# Vref.net
KiCad netlist of a schematic drawn in Altium Designer
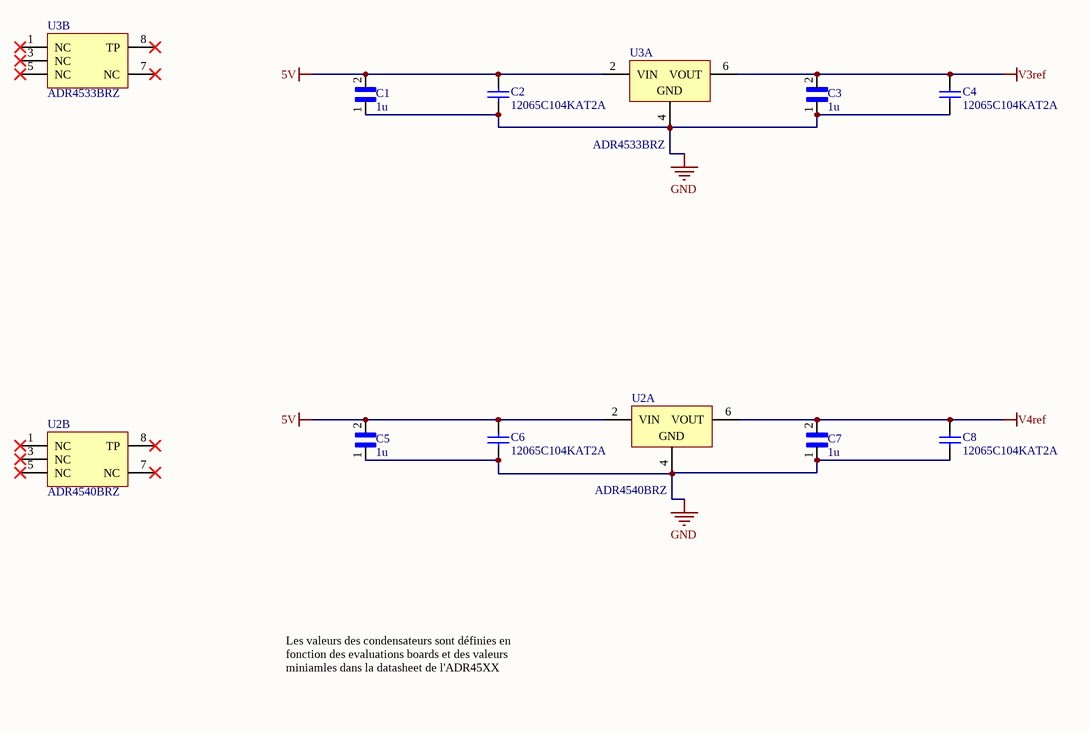
[diagram p0: Vref.SchDoc]

(export (version "E")
  (design (tool "Eeschema 10.0.6"))
  (components
    (comp (ref "C1")
      (value "1u")
      (footprint "1206YC105KAT2A:CAPC3216X127N")
      (description "Cap Ceramic 1uF 16V X7R 10% SMD 1206 125ÂÂŽ T/R")
      (fields (field (name "MF") "{'manufacturer': u'AVX'}") (field (name "MP") "1206YC105KAT2A"))
      (libsource (lib "1206YC105KAT2A") (part "1206YC105KAT2A"))
    )
    (comp (ref "C2")
      (value "12065C104KAT2A")
      (footprint "CAPC3216X94X50ML20T25")
      (description "Chip Capacitor, Ceramic, 100 nF, 10%, 50 V, 1206, RoHS, Tape and Reel")
      (fields (field (name "MANUFACTURER") "AVX"))
      (libsource (lib "Altium Content Vault") (part "CAP-NP-2"))
    )
    (comp (ref "C3")
      (value "1u")
      (footprint "1206YC105KAT2A:CAPC3216X127N")
      (description "Cap Ceramic 1uF 16V X7R 10% SMD 1206 125ÂÂŽ T/R")
      (fields (field (name "MF") "{'manufacturer': u'AVX'}") (field (name "MP") "1206YC105KAT2A"))
      (libsource (lib "1206YC105KAT2A") (part "1206YC105KAT2A"))
    )
    (comp (ref "C4")
      (value "12065C104KAT2A")
      (footprint "CAPC3216X94X50ML20T25")
      (description "Chip Capacitor, Ceramic, 100 nF, 10%, 50 V, 1206, RoHS, Tape and Reel")
      (fields (field (name "MANUFACTURER") "AVX"))
      (libsource (lib "Altium Content Vault") (part "CAP-NP-2"))
    )
    (comp (ref "C5")
      (value "1u")
      (footprint "1206YC105KAT2A:CAPC3216X127N")
      (description "Cap Ceramic 1uF 16V X7R 10% SMD 1206 125ÂÂŽ T/R")
      (fields (field (name "MF") "{'manufacturer': u'AVX'}") (field (name "MP") "1206YC105KAT2A"))
      (libsource (lib "1206YC105KAT2A") (part "1206YC105KAT2A"))
    )
    (comp (ref "C6")
      (value "12065C104KAT2A")
      (footprint "CAPC3216X94X50ML20T25")
      (description "Chip Capacitor, Ceramic, 100 nF, 10%, 50 V, 1206, RoHS, Tape and Reel")
      (fields (field (name "MANUFACTURER") "AVX"))
      (libsource (lib "Altium Content Vault") (part "CAP-NP-2"))
    )
    (comp (ref "C7")
      (value "1u")
      (footprint "1206YC105KAT2A:CAPC3216X127N")
      (description "Cap Ceramic 1uF 16V X7R 10% SMD 1206 125ÂÂŽ T/R")
      (fields (field (name "MF") "{'manufacturer': u'AVX'}") (field (name "MP") "1206YC105KAT2A"))
      (libsource (lib "1206YC105KAT2A") (part "1206YC105KAT2A"))
    )
    (comp (ref "C8")
      (value "12065C104KAT2A")
      (footprint "CAPC3216X94X50ML20T25")
      (description "Chip Capacitor, Ceramic, 100 nF, 10%, 50 V, 1206, RoHS, Tape and Reel")
      (fields (field (name "MANUFACTURER") "AVX"))
      (libsource (lib "Altium Content Vault") (part "CAP-NP-2"))
    )
    (comp (ref "U2")
      (value "ADR4540BRZ")
      (footprint "ADI-R-8_M")
      (fields (field (name "MANUFACTURER") "Analog Devices"))
      (libsource (lib "Altium Content Vault") (part "ADI-ADR45xx-R-8"))
    )
    (comp (ref "U3")
      (value "ADR4533BRZ")
      (footprint "ADI-R-8_L")
      (fields (field (name "MANUFACTURER") "Analog Devices"))
      (libsource (lib "Altium Content Vault") (part "ADI-ADR45xx-R-8"))
    )
  )
  (nets
    (net (code "1") (name "5V") (class "Default")
      (node (ref "C1") (pin "2") (pinfunction "2_2") (pintype "passive"))
      (node (ref "C2") (pin "1") (pinfunction "1_1") (pintype "passive"))
      (node (ref "C5") (pin "2") (pinfunction "2_2") (pintype "passive"))
      (node (ref "C6") (pin "1") (pinfunction "1_1") (pintype "passive"))
      (node (ref "U2") (pin "2") (pinfunction "VIN_2") (pintype "power_in"))
      (node (ref "U3") (pin "2") (pinfunction "VIN_2") (pintype "power_in"))
    )
    (net (code "2") (name "GND") (class "Default")
      (node (ref "C1") (pin "1") (pinfunction "1_1") (pintype "passive"))
      (node (ref "C2") (pin "2") (pinfunction "2_2") (pintype "passive"))
      (node (ref "C3") (pin "1") (pinfunction "1_1") (pintype "passive"))
      (node (ref "C4") (pin "2") (pinfunction "2_2") (pintype "passive"))
      (node (ref "C5") (pin "1") (pinfunction "1_1") (pintype "passive"))
      (node (ref "C6") (pin "2") (pinfunction "2_2") (pintype "passive"))
      (node (ref "C7") (pin "1") (pinfunction "1_1") (pintype "passive"))
      (node (ref "C8") (pin "2") (pinfunction "2_2") (pintype "passive"))
      (node (ref "U2") (pin "4") (pinfunction "GND_4") (pintype "power_in"))
      (node (ref "U3") (pin "4") (pinfunction "GND_4") (pintype "power_in"))
    )
    (net (code "3") (name "V3ref") (class "Default")
      (node (ref "C3") (pin "2") (pinfunction "2_2") (pintype "passive"))
      (node (ref "C4") (pin "1") (pinfunction "1_1") (pintype "passive"))
      (node (ref "U3") (pin "6") (pinfunction "VOUT_6") (pintype "power_in"))
    )
    (net (code "4") (name "V4ref") (class "Default")
      (node (ref "C7") (pin "2") (pinfunction "2_2") (pintype "passive"))
      (node (ref "C8") (pin "1") (pinfunction "1_1") (pintype "passive"))
      (node (ref "U2") (pin "6") (pinfunction "VOUT_6") (pintype "power_in"))
    )
    (net (code "5") (name "unconnected-(U2B-NC-Pad1)") (class "Default")
      (node (ref "U2") (pin "1") (pinfunction "NC_1") (pintype "passive+no_connect"))
    )
    (net (code "6") (name "unconnected-(U2B-NC-Pad3)") (class "Default")
      (node (ref "U2") (pin "3") (pinfunction "NC_3") (pintype "passive+no_connect"))
    )
    (net (code "7") (name "unconnected-(U2B-NC-Pad5)") (class "Default")
      (node (ref "U2") (pin "5") (pinfunction "NC_5") (pintype "passive+no_connect"))
    )
    (net (code "8") (name "unconnected-(U2B-NC-Pad7)") (class "Default")
      (node (ref "U2") (pin "7") (pinfunction "NC_7") (pintype "passive+no_connect"))
    )
    (net (code "9") (name "unconnected-(U2B-TP-Pad8)") (class "Default")
      (node (ref "U2") (pin "8") (pinfunction "TP_8") (pintype "passive+no_connect"))
    )
    (net (code "10") (name "unconnected-(U3B-NC-Pad1)") (class "Default")
      (node (ref "U3") (pin "1") (pinfunction "NC_1") (pintype "passive+no_connect"))
    )
    (net (code "11") (name "unconnected-(U3B-NC-Pad3)") (class "Default")
      (node (ref "U3") (pin "3") (pinfunction "NC_3") (pintype "passive+no_connect"))
    )
    (net (code "12") (name "unconnected-(U3B-NC-Pad5)") (class "Default")
      (node (ref "U3") (pin "5") (pinfunction "NC_5") (pintype "passive+no_connect"))
    )
    (net (code "13") (name "unconnected-(U3B-NC-Pad7)") (class "Default")
      (node (ref "U3") (pin "7") (pinfunction "NC_7") (pintype "passive+no_connect"))
    )
    (net (code "14") (name "unconnected-(U3B-TP-Pad8)") (class "Default")
      (node (ref "U3") (pin "8") (pinfunction "TP_8") (pintype "passive+no_connect"))
    )
  )
)
